# Sheet1.net
KiCad netlist of a schematic drawn in Altium Designer
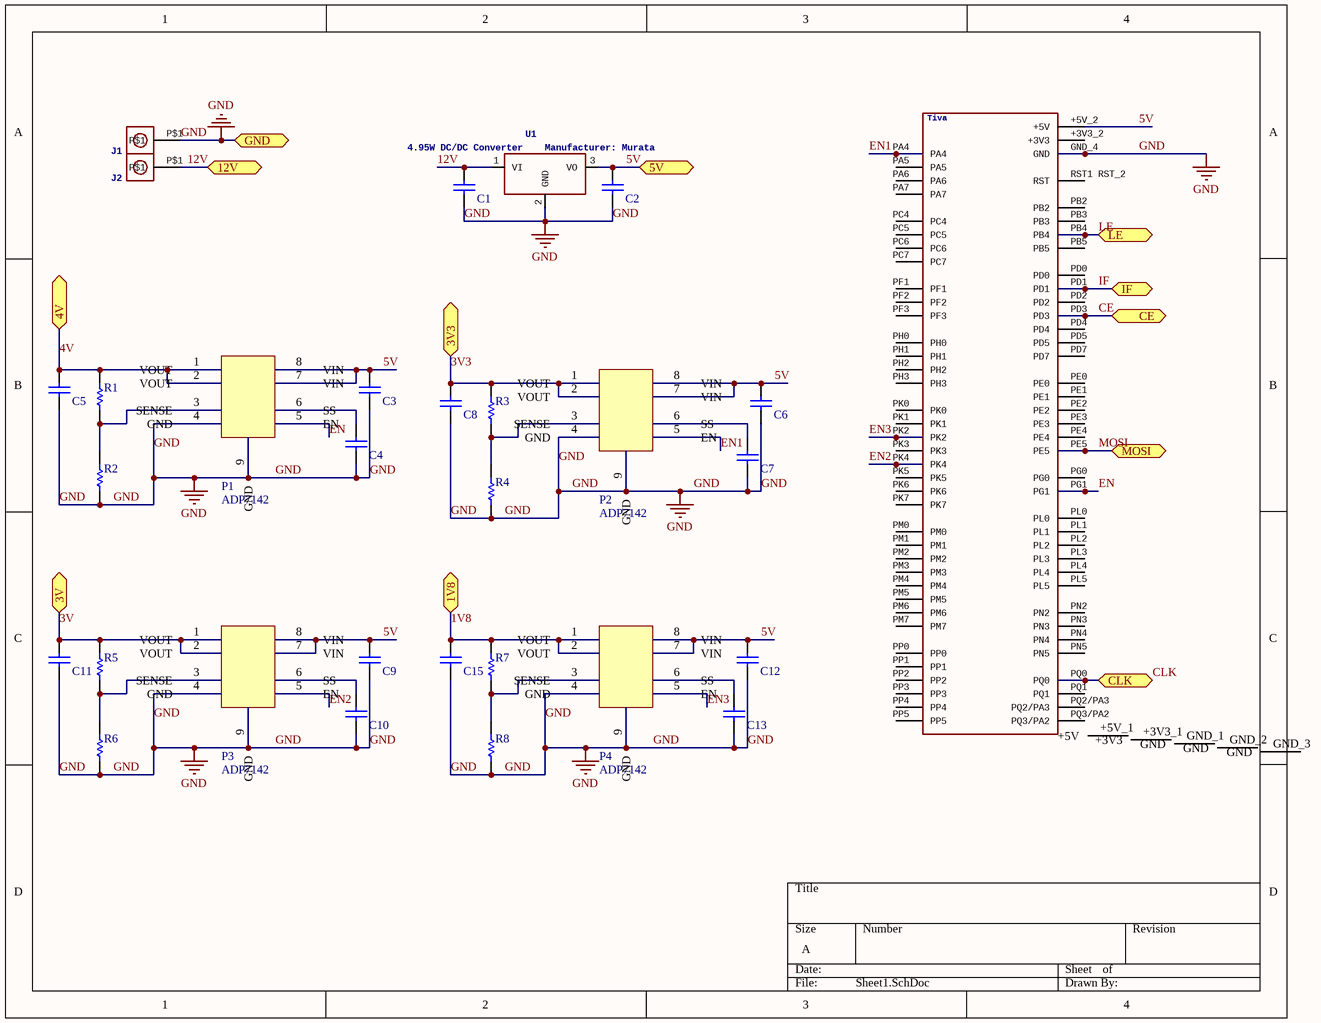
[diagram p0: Sheet1.SchDoc]

(export (version "E")
  (design (tool "Eeschema 10.0.6"))
  (components
    (comp (ref "C1")
      (value "CAP 10uF 16V 0603(1608)")
      (footprint "CAPC0603(1608)100_L")
      (description "CAP 10uF 16V ±1% 0603 (1608 Metric) Thickness 1mm SMD")
      (fields (field (name "TOLERANCE") "Â±1%"))
      (libsource (lib "Altium Content Vault") (part "CMP-1035-01744-1"))
    )
    (comp (ref "C2")
      (value "CAP 22uF 16V 0603(1608)")
      (footprint "CAPC0603(1608)100_L")
      (description "CAP 22uF 16V ±1% 0603 (1608 Metric) Thickness 1mm SMD")
      (fields (field (name "TOLERANCE") "Â±1%"))
      (libsource (lib "Altium Content Vault") (part "CMP-1035-01744-1"))
    )
    (comp (ref "C3")
      (value "CAP 2.2uF 16V 0603(1608)")
      (footprint "CAPC0603(1608)100_L")
      (description "CAP 2.2uF 16V ±1% 0603 (1608 Metric) Thickness 1mm SMD")
      (fields (field (name "TOLERANCE") "Â±1%"))
      (libsource (lib "Altium Content Vault") (part "CMP-1035-01744-1"))
    )
    (comp (ref "C4")
      (value "CAP 1nF 16V 0603(1608)")
      (footprint "CAPC0603(1608)100_L")
      (description "CAP 1nF 16V ±1% 0603 (1608 Metric) Thickness 1mm SMD")
      (fields (field (name "TOLERANCE") "Â±1%"))
      (libsource (lib "Altium Content Vault") (part "CMP-1035-01744-1"))
    )
    (comp (ref "C5")
      (value "CAP 2.2uF 16V 0603(1608)")
      (footprint "CAPC0603(1608)100_L")
      (description "CAP 2.2uF 16V ±1% 0603 (1608 Metric) Thickness 1mm SMD")
      (fields (field (name "TOLERANCE") "Â±1%"))
      (libsource (lib "Altium Content Vault") (part "CMP-1035-01744-1"))
    )
    (comp (ref "C6")
      (value "CAP 2.2uF 16V 0603(1608)")
      (footprint "CAPC0603(1608)100_L")
      (description "CAP 2.2uF 16V ±1% 0603 (1608 Metric) Thickness 1mm SMD")
      (fields (field (name "TOLERANCE") "Â±1%"))
      (libsource (lib "Altium Content Vault") (part "CMP-1035-01744-1"))
    )
    (comp (ref "C7")
      (value "CAP 1nF 16V 0603(1608)")
      (footprint "CAPC0603(1608)100_L")
      (description "CAP 1nF 16V ±1% 0603 (1608 Metric) Thickness 1mm SMD")
      (fields (field (name "TOLERANCE") "Â±1%"))
      (libsource (lib "Altium Content Vault") (part "CMP-1035-01744-1"))
    )
    (comp (ref "C8")
      (value "CAP 2.2uF 16V 0603(1608)")
      (footprint "CAPC0603(1608)100_L")
      (description "CAP 2.2uF 16V ±1% 0603 (1608 Metric) Thickness 1mm SMD")
      (fields (field (name "TOLERANCE") "Â±1%"))
      (libsource (lib "Altium Content Vault") (part "CMP-1035-01744-1"))
    )
    (comp (ref "C9")
      (value "CAP 2.2uF 16V 0603(1608)")
      (footprint "CAPC0603(1608)100_L")
      (description "CAP 2.2uF 16V ±1% 0603 (1608 Metric) Thickness 1mm SMD")
      (fields (field (name "TOLERANCE") "Â±1%"))
      (libsource (lib "Altium Content Vault") (part "CMP-1035-01744-1"))
    )
    (comp (ref "C10")
      (value "CAP 1nF 16V 0603(1608)")
      (footprint "CAPC0603(1608)100_L")
      (description "CAP 1nF 16V ±1% 0603 (1608 Metric) Thickness 1mm SMD")
      (fields (field (name "TOLERANCE") "Â±1%"))
      (libsource (lib "Altium Content Vault") (part "CMP-1035-01744-1"))
    )
    (comp (ref "C11")
      (value "CAP 2.2uF 16V 0603(1608)")
      (footprint "CAPC0603(1608)100_L")
      (description "CAP 2.2uF 16V ±1% 0603 (1608 Metric) Thickness 1mm SMD")
      (fields (field (name "TOLERANCE") "Â±1%"))
      (libsource (lib "Altium Content Vault") (part "CMP-1035-01744-1"))
    )
    (comp (ref "C12")
      (value "CAP 2.2uF 16V 0603(1608)")
      (footprint "CAPC0603(1608)100_L")
      (description "CAP 2.2uF 16V ±1% 0603 (1608 Metric) Thickness 1mm SMD")
      (fields (field (name "TOLERANCE") "Â±1%"))
      (libsource (lib "Altium Content Vault") (part "CMP-1035-01744-1"))
    )
    (comp (ref "C13")
      (value "CAP 1nF 16V 0603(1608)")
      (footprint "CAPC0603(1608)100_L")
      (description "CAP 1nF 16V ±1% 0603 (1608 Metric) Thickness 1mm SMD")
      (fields (field (name "TOLERANCE") "Â±1%"))
      (libsource (lib "Altium Content Vault") (part "CMP-1035-01744-1"))
    )
    (comp (ref "C15")
      (value "CAP 2.2uF 16V 0603(1608)")
      (footprint "CAPC0603(1608)100_L")
      (description "CAP 2.2uF 16V ±1% 0603 (1608 Metric) Thickness 1mm SMD")
      (fields (field (name "TOLERANCE") "Â±1%"))
      (libsource (lib "Altium Content Vault") (part "CMP-1035-01744-1"))
    )
    (comp (ref "J1")
      (value "http://www.powerwerx.com/anderson-powerpoles/")
      (footprint "APP45_PCB_HORIZ_RIGHT")
      (libsource (lib "MRDT-Connectors") (part "APPPP45_PCB_HORIZ_RIGHT"))
    )
    (comp (ref "J2")
      (value "http://www.powerwerx.com/anderson-powerpoles/")
      (footprint "APP45_PCB_HORIZ_RIGHT")
      (libsource (lib "MRDT-Connectors") (part "APPPP45_PCB_HORIZ_RIGHT"))
    )
    (comp (ref "P1")
      (value "ADP7142")
      (footprint "SOIC127P600X175_HS-9N")
      (libsource (lib "ADP7142") (part "ADP7142"))
    )
    (comp (ref "P2")
      (value "ADP7142")
      (footprint "SOIC127P600X175_HS-9N")
      (libsource (lib "ADP7142") (part "ADP7142"))
    )
    (comp (ref "P3")
      (value "ADP7142")
      (footprint "SOIC127P600X175_HS-9N")
      (libsource (lib "ADP7142") (part "ADP7142"))
    )
    (comp (ref "P4")
      (value "ADP7142")
      (footprint "SOIC127P600X175_HS-9N")
      (libsource (lib "ADP7142") (part "ADP7142"))
    )
    (comp (ref "R1")
      (value "500 1% 0603(1608)")
      (footprint "RESC0603(1608)_N")
      (description "500 0.1W 1% 0603 (1608 Metric)  SMD")
      (fields (field (name "POWER") "0.1 W") (field (name "TOLERANCE") "1 %"))
      (libsource (lib "Altium Content Vault") (part "CMP-1012-00736-1"))
    )
    (comp (ref "R2")
      (value "215 1% 0603(1608)")
      (footprint "RESC0603(1608)_N")
      (description "215 0.1W 1% 0603 (1608 Metric)  SMD")
      (fields (field (name "POWER") "0.1 W") (field (name "TOLERANCE") "1 %"))
      (libsource (lib "Altium Content Vault") (part "CMP-1012-00736-1"))
    )
    (comp (ref "R3")
      (value "500 1% 0603(1608)")
      (footprint "RESC0603(1608)_N")
      (description "500 0.1W 1% 0603 (1608 Metric)  SMD")
      (fields (field (name "POWER") "0.1 W") (field (name "TOLERANCE") "1 %"))
      (libsource (lib "Altium Content Vault") (part "CMP-1012-00736-1"))
    )
    (comp (ref "R4")
      (value "287 1% 0603(1608)")
      (footprint "RESC0603(1608)_N")
      (description "287 0.1W 1% 0603 (1608 Metric)  SMD")
      (fields (field (name "POWER") "0.1 W") (field (name "TOLERANCE") "1 %"))
      (libsource (lib "Altium Content Vault") (part "CMP-1012-00736-1"))
    )
    (comp (ref "R5")
      (value "500 1% 0603(1608)")
      (footprint "RESC0603(1608)_N")
      (description "500 0.1W 1% 0603 (1608 Metric)  SMD")
      (fields (field (name "POWER") "0.1 W") (field (name "TOLERANCE") "1 %"))
      (libsource (lib "Altium Content Vault") (part "CMP-1012-00736-1"))
    )
    (comp (ref "R6")
      (value "332 1% 0603(1608)")
      (footprint "RESC0603(1608)_N")
      (description "332 0.1W 1% 0603 (1608 Metric)  SMD")
      (fields (field (name "POWER") "0.1 W") (field (name "TOLERANCE") "1 %"))
      (libsource (lib "Altium Content Vault") (part "CMP-1012-00736-1"))
    )
    (comp (ref "R7")
      (value "1000 1% 0603(1608)")
      (footprint "RESC0603(1608)_N")
      (description "1000 0.1W 1% 0603 (1608 Metric)  SMD")
      (fields (field (name "POWER") "0.1 W") (field (name "TOLERANCE") "1 %"))
      (libsource (lib "Altium Content Vault") (part "CMP-1012-00736-1"))
    )
    (comp (ref "R8")
      (value "500 1% 0603(1608)")
      (footprint "RESC0603(1608)_N")
      (description "500 0.1W 1% 0603 (1608 Metric)  SMD")
      (fields (field (name "POWER") "0.1 W") (field (name "TOLERANCE") "1 %"))
      (libsource (lib "Altium Content Vault") (part "CMP-1012-00736-1"))
    )
    (comp (ref "Tiva")
      (value "TIVA C CONNECTED LAUNCHPAD")
      (footprint "TIVA-C-CONNECTED")
      (libsource (lib "MRDT-Microcontrollers") (part "TIVA-1294"))
    )
    (comp (ref "U1")
      (value "4.95W DC/DC Converter    Manufacturer: Murata")
      (footprint "OKI-78SR_HORIZ")
      (description "12 to 5V converter")
      (libsource (lib "MRDT-ICs") (part "OKI-78SR-*/1.5-W36?CH"))
    )
  )
  (nets
    (net (code "1") (name "/1V8") (class "Default")
      (node (ref "C15") (pin "1") (pinfunction "1_1") (pintype "passive"))
      (node (ref "P4") (pin "1") (pinfunction "VOUT_1") (pintype "passive"))
      (node (ref "P4") (pin "2") (pinfunction "VOUT_2") (pintype "passive"))
      (node (ref "R7") (pin "2") (pinfunction "2_2") (pintype "passive"))
    )
    (net (code "2") (name "/3V") (class "Default")
      (node (ref "C11") (pin "1") (pinfunction "1_1") (pintype "passive"))
      (node (ref "P3") (pin "1") (pinfunction "VOUT_1") (pintype "passive"))
      (node (ref "P3") (pin "2") (pinfunction "VOUT_2") (pintype "passive"))
      (node (ref "R5") (pin "2") (pinfunction "2_2") (pintype "passive"))
    )
    (net (code "3") (name "/3V3") (class "Default")
      (node (ref "C8") (pin "1") (pinfunction "1_1") (pintype "passive"))
      (node (ref "P2") (pin "1") (pinfunction "VOUT_1") (pintype "passive"))
      (node (ref "P2") (pin "2") (pinfunction "VOUT_2") (pintype "passive"))
      (node (ref "R3") (pin "2") (pinfunction "2_2") (pintype "passive"))
    )
    (net (code "4") (name "/4V") (class "Default")
      (node (ref "C5") (pin "1") (pinfunction "1_1") (pintype "passive"))
      (node (ref "P1") (pin "1") (pinfunction "VOUT_1") (pintype "passive"))
      (node (ref "P1") (pin "2") (pinfunction "VOUT_2") (pintype "passive"))
      (node (ref "R1") (pin "2") (pinfunction "2_2") (pintype "passive"))
    )
    (net (code "5") (name "/5V") (class "Default")
      (node (ref "C12") (pin "1") (pinfunction "1_1") (pintype "passive"))
      (node (ref "C2") (pin "1") (pinfunction "1_1") (pintype "passive"))
      (node (ref "C3") (pin "1") (pinfunction "1_1") (pintype "passive"))
      (node (ref "C6") (pin "1") (pinfunction "1_1") (pintype "passive"))
      (node (ref "C9") (pin "1") (pinfunction "1_1") (pintype "passive"))
      (node (ref "P1") (pin "7") (pinfunction "VIN_7") (pintype "passive"))
      (node (ref "P1") (pin "8") (pinfunction "VIN_8") (pintype "passive"))
      (node (ref "P2") (pin "7") (pinfunction "VIN_7") (pintype "passive"))
      (node (ref "P2") (pin "8") (pinfunction "VIN_8") (pintype "passive"))
      (node (ref "P3") (pin "7") (pinfunction "VIN_7") (pintype "passive"))
      (node (ref "P3") (pin "8") (pinfunction "VIN_8") (pintype "passive"))
      (node (ref "P4") (pin "7") (pinfunction "VIN_7") (pintype "passive"))
      (node (ref "P4") (pin "8") (pinfunction "VIN_8") (pintype "passive"))
      (node (ref "Tiva") (pin "+5V_2") (pinfunction "+5V_+5V_2") (pintype "passive"))
      (node (ref "U1") (pin "3") (pinfunction "VO_3") (pintype "passive"))
    )
    (net (code "6") (name "/12V") (class "Default")
      (node (ref "C1") (pin "1") (pinfunction "1_1") (pintype "passive"))
      (node (ref "J2") (pin "P$1") (pinfunction "P$1_P$1") (pintype "power_in"))
      (node (ref "U1") (pin "1") (pinfunction "VI_1") (pintype "passive"))
    )
    (net (code "7") (name "/CE") (class "Default")
      (node (ref "Tiva") (pin "PD3") (pinfunction "PD3_PD3") (pintype "passive"))
    )
    (net (code "8") (name "/CLK") (class "Default")
      (node (ref "Tiva") (pin "PQ0") (pinfunction "PQ0_PQ0") (pintype "passive"))
    )
    (net (code "9") (name "/EN") (class "Default")
      (node (ref "P1") (pin "5") (pinfunction "EN_5") (pintype "passive"))
      (node (ref "Tiva") (pin "PG1") (pinfunction "PG1_PG1") (pintype "passive"))
    )
    (net (code "10") (name "/EN1") (class "Default")
      (node (ref "P2") (pin "5") (pinfunction "EN_5") (pintype "passive"))
      (node (ref "Tiva") (pin "PA4") (pinfunction "PA4_PA4") (pintype "passive"))
    )
    (net (code "11") (name "/EN2") (class "Default")
      (node (ref "P3") (pin "5") (pinfunction "EN_5") (pintype "passive"))
      (node (ref "Tiva") (pin "PK4") (pinfunction "PK4_PK4") (pintype "passive"))
    )
    (net (code "12") (name "/EN3") (class "Default")
      (node (ref "P4") (pin "5") (pinfunction "EN_5") (pintype "passive"))
      (node (ref "Tiva") (pin "PK2") (pinfunction "PK2_PK2") (pintype "passive"))
    )
    (net (code "13") (name "/IF") (class "Default")
      (node (ref "Tiva") (pin "PD1") (pinfunction "PD1_PD1") (pintype "passive"))
    )
    (net (code "14") (name "/LE") (class "Default")
      (node (ref "Tiva") (pin "PB4") (pinfunction "PB4_PB4") (pintype "passive"))
    )
    (net (code "15") (name "/MOSI") (class "Default")
      (node (ref "Tiva") (pin "PE5") (pinfunction "PE5_PE5") (pintype "passive"))
    )
    (net (code "16") (name "GND") (class "Default")
      (node (ref "C1") (pin "2") (pinfunction "2_2") (pintype "passive"))
      (node (ref "C10") (pin "2") (pinfunction "2_2") (pintype "passive"))
      (node (ref "C11") (pin "2") (pinfunction "2_2") (pintype "passive"))
      (node (ref "C12") (pin "2") (pinfunction "2_2") (pintype "passive"))
      (node (ref "C13") (pin "2") (pinfunction "2_2") (pintype "passive"))
      (node (ref "C15") (pin "2") (pinfunction "2_2") (pintype "passive"))
      (node (ref "C2") (pin "2") (pinfunction "2_2") (pintype "passive"))
      (node (ref "C3") (pin "2") (pinfunction "2_2") (pintype "passive"))
      (node (ref "C4") (pin "2") (pinfunction "2_2") (pintype "passive"))
      (node (ref "C5") (pin "2") (pinfunction "2_2") (pintype "passive"))
      (node (ref "C6") (pin "2") (pinfunction "2_2") (pintype "passive"))
      (node (ref "C7") (pin "2") (pinfunction "2_2") (pintype "passive"))
      (node (ref "C8") (pin "2") (pinfunction "2_2") (pintype "passive"))
      (node (ref "C9") (pin "2") (pinfunction "2_2") (pintype "passive"))
      (node (ref "J1") (pin "P$1") (pinfunction "P$1_P$1") (pintype "power_in"))
      (node (ref "P1") (pin "4") (pinfunction "GND_4") (pintype "passive"))
      (node (ref "P1") (pin "9") (pinfunction "GND_9") (pintype "passive"))
      (node (ref "P2") (pin "4") (pinfunction "GND_4") (pintype "passive"))
      (node (ref "P2") (pin "9") (pinfunction "GND_9") (pintype "passive"))
      (node (ref "P3") (pin "4") (pinfunction "GND_4") (pintype "passive"))
      (node (ref "P3") (pin "9") (pinfunction "GND_9") (pintype "passive"))
      (node (ref "P4") (pin "4") (pinfunction "GND_4") (pintype "passive"))
      (node (ref "P4") (pin "9") (pinfunction "GND_9") (pintype "passive"))
      (node (ref "R2") (pin "1") (pinfunction "1_1") (pintype "passive"))
      (node (ref "R4") (pin "1") (pinfunction "1_1") (pintype "passive"))
      (node (ref "R6") (pin "1") (pinfunction "1_1") (pintype "passive"))
      (node (ref "R8") (pin "1") (pinfunction "1_1") (pintype "passive"))
      (node (ref "Tiva") (pin "GND_4") (pinfunction "GND_GND_4") (pintype "power_in"))
      (node (ref "U1") (pin "2") (pinfunction "GND_2") (pintype "power_in"))
    )
    (net (code "17") (name "Net-(P1-SENSE)") (class "Default")
      (node (ref "P1") (pin "3") (pinfunction "SENSE_3") (pintype "passive"))
      (node (ref "R1") (pin "1") (pinfunction "1_1") (pintype "passive"))
      (node (ref "R2") (pin "2") (pinfunction "2_2") (pintype "passive"))
    )
    (net (code "18") (name "Net-(P1-SS)") (class "Default")
      (node (ref "C4") (pin "1") (pinfunction "1_1") (pintype "passive"))
      (node (ref "P1") (pin "6") (pinfunction "SS_6") (pintype "passive"))
    )
    (net (code "19") (name "Net-(P2-SENSE)") (class "Default")
      (node (ref "P2") (pin "3") (pinfunction "SENSE_3") (pintype "passive"))
      (node (ref "R3") (pin "1") (pinfunction "1_1") (pintype "passive"))
      (node (ref "R4") (pin "2") (pinfunction "2_2") (pintype "passive"))
    )
    (net (code "20") (name "Net-(P2-SS)") (class "Default")
      (node (ref "C7") (pin "1") (pinfunction "1_1") (pintype "passive"))
      (node (ref "P2") (pin "6") (pinfunction "SS_6") (pintype "passive"))
    )
    (net (code "21") (name "Net-(P3-SENSE)") (class "Default")
      (node (ref "P3") (pin "3") (pinfunction "SENSE_3") (pintype "passive"))
      (node (ref "R5") (pin "1") (pinfunction "1_1") (pintype "passive"))
      (node (ref "R6") (pin "2") (pinfunction "2_2") (pintype "passive"))
    )
    (net (code "22") (name "Net-(P3-SS)") (class "Default")
      (node (ref "C10") (pin "1") (pinfunction "1_1") (pintype "passive"))
      (node (ref "P3") (pin "6") (pinfunction "SS_6") (pintype "passive"))
    )
    (net (code "23") (name "Net-(P4-SENSE)") (class "Default")
      (node (ref "P4") (pin "3") (pinfunction "SENSE_3") (pintype "passive"))
      (node (ref "R7") (pin "1") (pinfunction "1_1") (pintype "passive"))
      (node (ref "R8") (pin "2") (pinfunction "2_2") (pintype "passive"))
    )
    (net (code "24") (name "Net-(P4-SS)") (class "Default")
      (node (ref "C13") (pin "1") (pinfunction "1_1") (pintype "passive"))
      (node (ref "P4") (pin "6") (pinfunction "SS_6") (pintype "passive"))
    )
    (net (code "25") (name "unconnected-(Tiva-+3V3-Pad+3V3_1)") (class "Default")
      (node (ref "Tiva") (pin "+3V3_1") (pinfunction "+3V3_+3V3_1") (pintype "passive"))
    )
    (net (code "26") (name "unconnected-(Tiva-+3V3-Pad+3V3_2)") (class "Default")
      (node (ref "Tiva") (pin "+3V3_2") (pinfunction "+3V3_+3V3_2") (pintype "passive"))
    )
    (net (code "27") (name "unconnected-(Tiva-+5V-Pad+5V_1)") (class "Default")
      (node (ref "Tiva") (pin "+5V_1") (pinfunction "+5V_+5V_1") (pintype "passive"))
    )
    (net (code "28") (name "unconnected-(Tiva-GND-PadGND_1)") (class "Default")
      (node (ref "Tiva") (pin "GND_1") (pinfunction "GND_GND_1") (pintype "passive"))
    )
    (net (code "29") (name "unconnected-(Tiva-GND-PadGND_2)") (class "Default")
      (node (ref "Tiva") (pin "GND_2") (pinfunction "GND_GND_2") (pintype "passive"))
    )
    (net (code "30") (name "unconnected-(Tiva-GND-PadGND_3)") (class "Default")
      (node (ref "Tiva") (pin "GND_3") (pinfunction "GND_GND_3") (pintype "passive"))
    )
    (net (code "31") (name "unconnected-(Tiva-PadPA5)") (class "Default")
      (node (ref "Tiva") (pin "PA5") (pinfunction "PA5_PA5") (pintype "passive"))
    )
    (net (code "32") (name "unconnected-(Tiva-PadPA6)") (class "Default")
      (node (ref "Tiva") (pin "PA6") (pinfunction "PA6_PA6") (pintype "passive"))
    )
    (net (code "33") (name "unconnected-(Tiva-PadPA7)") (class "Default")
      (node (ref "Tiva") (pin "PA7") (pinfunction "PA7_PA7") (pintype "passive"))
    )
    (net (code "34") (name "unconnected-(Tiva-PadPB2)") (class "Default")
      (node (ref "Tiva") (pin "PB2") (pinfunction "PB2_PB2") (pintype "passive"))
    )
    (net (code "35") (name "unconnected-(Tiva-PadPB3)") (class "Default")
      (node (ref "Tiva") (pin "PB3") (pinfunction "PB3_PB3") (pintype "passive"))
    )
    (net (code "36") (name "unconnected-(Tiva-PadPB5)") (class "Default")
      (node (ref "Tiva") (pin "PB5") (pinfunction "PB5_PB5") (pintype "passive"))
    )
    (net (code "37") (name "unconnected-(Tiva-PadPC4)") (class "Default")
      (node (ref "Tiva") (pin "PC4") (pinfunction "PC4_PC4") (pintype "passive"))
    )
    (net (code "38") (name "unconnected-(Tiva-PadPC5)") (class "Default")
      (node (ref "Tiva") (pin "PC5") (pinfunction "PC5_PC5") (pintype "passive"))
    )
    (net (code "39") (name "unconnected-(Tiva-PadPC6)") (class "Default")
      (node (ref "Tiva") (pin "PC6") (pinfunction "PC6_PC6") (pintype "passive"))
    )
    (net (code "40") (name "unconnected-(Tiva-PadPC7)") (class "Default")
      (node (ref "Tiva") (pin "PC7") (pinfunction "PC7_PC7") (pintype "passive"))
    )
    (net (code "41") (name "unconnected-(Tiva-PadPD0)") (class "Default")
      (node (ref "Tiva") (pin "PD0") (pinfunction "PD0_PD0") (pintype "passive"))
    )
    (net (code "42") (name "unconnected-(Tiva-PadPD2)") (class "Default")
      (node (ref "Tiva") (pin "PD2") (pinfunction "PD2_PD2") (pintype "passive"))
    )
    (net (code "43") (name "unconnected-(Tiva-PadPD4)") (class "Default")
      (node (ref "Tiva") (pin "PD4") (pinfunction "PD4_PD4") (pintype "passive"))
    )
    (net (code "44") (name "unconnected-(Tiva-PadPD5)") (class "Default")
      (node (ref "Tiva") (pin "PD5") (pinfunction "PD5_PD5") (pintype "passive"))
    )
    (net (code "45") (name "unconnected-(Tiva-PadPD7)") (class "Default")
      (node (ref "Tiva") (pin "PD7") (pinfunction "PD7_PD7") (pintype "passive"))
    )
    (net (code "46") (name "unconnected-(Tiva-PadPE0)") (class "Default")
      (node (ref "Tiva") (pin "PE0") (pinfunction "PE0_PE0") (pintype "passive"))
    )
    (net (code "47") (name "unconnected-(Tiva-PadPE1)") (class "Default")
      (node (ref "Tiva") (pin "PE1") (pinfunction "PE1_PE1") (pintype "passive"))
    )
    (net (code "48") (name "unconnected-(Tiva-PadPE2)") (class "Default")
      (node (ref "Tiva") (pin "PE2") (pinfunction "PE2_PE2") (pintype "passive"))
    )
    (net (code "49") (name "unconnected-(Tiva-PadPE3)") (class "Default")
      (node (ref "Tiva") (pin "PE3") (pinfunction "PE3_PE3") (pintype "passive"))
    )
    (net (code "50") (name "unconnected-(Tiva-PadPE4)") (class "Default")
      (node (ref "Tiva") (pin "PE4") (pinfunction "PE4_PE4") (pintype "passive"))
    )
    (net (code "51") (name "unconnected-(Tiva-PadPF1)") (class "Default")
      (node (ref "Tiva") (pin "PF1") (pinfunction "PF1_PF1") (pintype "passive"))
    )
    (net (code "52") (name "unconnected-(Tiva-PadPF2)") (class "Default")
      (node (ref "Tiva") (pin "PF2") (pinfunction "PF2_PF2") (pintype "passive"))
    )
    (net (code "53") (name "unconnected-(Tiva-PadPF3)") (class "Default")
      (node (ref "Tiva") (pin "PF3") (pinfunction "PF3_PF3") (pintype "passive"))
    )
    (net (code "54") (name "unconnected-(Tiva-PadPG0)") (class "Default")
      (node (ref "Tiva") (pin "PG0") (pinfunction "PG0_PG0") (pintype "passive"))
    )
    (net (code "55") (name "unconnected-(Tiva-PadPH0)") (class "Default")
      (node (ref "Tiva") (pin "PH0") (pinfunction "PH0_PH0") (pintype "passive"))
    )
    (net (code "56") (name "unconnected-(Tiva-PadPH1)") (class "Default")
      (node (ref "Tiva") (pin "PH1") (pinfunction "PH1_PH1") (pintype "passive"))
    )
    (net (code "57") (name "unconnected-(Tiva-PadPH2)") (class "Default")
      (node (ref "Tiva") (pin "PH2") (pinfunction "PH2_PH2") (pintype "passive"))
    )
    (net (code "58") (name "unconnected-(Tiva-PadPH3)") (class "Default")
      (node (ref "Tiva") (pin "PH3") (pinfunction "PH3_PH3") (pintype "passive"))
    )
    (net (code "59") (name "unconnected-(Tiva-PadPK0)") (class "Default")
      (node (ref "Tiva") (pin "PK0") (pinfunction "PK0_PK0") (pintype "passive"))
    )
    (net (code "60") (name "unconnected-(Tiva-PadPK1)") (class "Default")
      (node (ref "Tiva") (pin "PK1") (pinfunction "PK1_PK1") (pintype "passive"))
    )
    (net (code "61") (name "unconnected-(Tiva-PadPK3)") (class "Default")
      (node (ref "Tiva") (pin "PK3") (pinfunction "PK3_PK3") (pintype "passive"))
    )
    (net (code "62") (name "unconnected-(Tiva-PadPK5)") (class "Default")
      (node (ref "Tiva") (pin "PK5") (pinfunction "PK5_PK5") (pintype "passive"))
    )
    (net (code "63") (name "unconnected-(Tiva-PadPK6)") (class "Default")
      (node (ref "Tiva") (pin "PK6") (pinfunction "PK6_PK6") (pintype "passive"))
    )
    (net (code "64") (name "unconnected-(Tiva-PadPK7)") (class "Default")
      (node (ref "Tiva") (pin "PK7") (pinfunction "PK7_PK7") (pintype "passive"))
    )
    (net (code "65") (name "unconnected-(Tiva-PadPL0)") (class "Default")
      (node (ref "Tiva") (pin "PL0") (pinfunction "PL0_PL0") (pintype "passive"))
    )
    (net (code "66") (name "unconnected-(Tiva-PadPL1)") (class "Default")
      (node (ref "Tiva") (pin "PL1") (pinfunction "PL1_PL1") (pintype "passive"))
    )
    (net (code "67") (name "unconnected-(Tiva-PadPL2)") (class "Default")
      (node (ref "Tiva") (pin "PL2") (pinfunction "PL2_PL2") (pintype "passive"))
    )
    (net (code "68") (name "unconnected-(Tiva-PadPL3)") (class "Default")
      (node (ref "Tiva") (pin "PL3") (pinfunction "PL3_PL3") (pintype "passive"))
    )
    (net (code "69") (name "unconnected-(Tiva-PadPL4)") (class "Default")
      (node (ref "Tiva") (pin "PL4") (pinfunction "PL4_PL4") (pintype "passive"))
    )
    (net (code "70") (name "unconnected-(Tiva-PadPL5)") (class "Default")
      (node (ref "Tiva") (pin "PL5") (pinfunction "PL5_PL5") (pintype "passive"))
    )
    (net (code "71") (name "unconnected-(Tiva-PadPM0)") (class "Default")
      (node (ref "Tiva") (pin "PM0") (pinfunction "PM0_PM0") (pintype "passive"))
    )
    (net (code "72") (name "unconnected-(Tiva-PadPM1)") (class "Default")
      (node (ref "Tiva") (pin "PM1") (pinfunction "PM1_PM1") (pintype "passive"))
    )
    (net (code "73") (name "unconnected-(Tiva-PadPM2)") (class "Default")
      (node (ref "Tiva") (pin "PM2") (pinfunction "PM2_PM2") (pintype "passive"))
    )
    (net (code "74") (name "unconnected-(Tiva-PadPM3)") (class "Default")
      (node (ref "Tiva") (pin "PM3") (pinfunction "PM3_PM3") (pintype "passive"))
    )
    (net (code "75") (name "unconnected-(Tiva-PadPM4)") (class "Default")
      (node (ref "Tiva") (pin "PM4") (pinfunction "PM4_PM4") (pintype "passive"))
    )
    (net (code "76") (name "unconnected-(Tiva-PadPM5)") (class "Default")
      (node (ref "Tiva") (pin "PM5") (pinfunction "PM5_PM5") (pintype "passive"))
    )
    (net (code "77") (name "unconnected-(Tiva-PadPM6)") (class "Default")
      (node (ref "Tiva") (pin "PM6") (pinfunction "PM6_PM6") (pintype "passive"))
    )
    (net (code "78") (name "unconnected-(Tiva-PadPM7)") (class "Default")
      (node (ref "Tiva") (pin "PM7") (pinfunction "PM7_PM7") (pintype "passive"))
    )
    (net (code "79") (name "unconnected-(Tiva-PadPN2)") (class "Default")
      (node (ref "Tiva") (pin "PN2") (pinfunction "PN2_PN2") (pintype "passive"))
    )
    (net (code "80") (name "unconnected-(Tiva-PadPN3)") (class "Default")
      (node (ref "Tiva") (pin "PN3") (pinfunction "PN3_PN3") (pintype "passive"))
    )
    (net (code "81") (name "unconnected-(Tiva-PadPN4)") (class "Default")
      (node (ref "Tiva") (pin "PN4") (pinfunction "PN4_PN4") (pintype "passive"))
    )
    (net (code "82") (name "unconnected-(Tiva-PadPN5)") (class "Default")
      (node (ref "Tiva") (pin "PN5") (pinfunction "PN5_PN5") (pintype "passive"))
    )
    (net (code "83") (name "unconnected-(Tiva-PadPP0)") (class "Default")
      (node (ref "Tiva") (pin "PP0") (pinfunction "PP0_PP0") (pintype "passive"))
    )
    (net (code "84") (name "unconnected-(Tiva-PadPP1)") (class "Default")
      (node (ref "Tiva") (pin "PP1") (pinfunction "PP1_PP1") (pintype "passive"))
    )
    (net (code "85") (name "unconnected-(Tiva-PadPP2)") (class "Default")
      (node (ref "Tiva") (pin "PP2") (pinfunction "PP2_PP2") (pintype "passive"))
    )
    (net (code "86") (name "unconnected-(Tiva-PadPP3)") (class "Default")
      (node (ref "Tiva") (pin "PP3") (pinfunction "PP3_PP3") (pintype "passive"))
    )
    (net (code "87") (name "unconnected-(Tiva-PadPP4)") (class "Default")
      (node (ref "Tiva") (pin "PP4") (pinfunction "PP4_PP4") (pintype "passive"))
    )
    (net (code "88") (name "unconnected-(Tiva-PadPP5)") (class "Default")
      (node (ref "Tiva") (pin "PP5") (pinfunction "PP5_PP5") (pintype "passive"))
    )
    (net (code "89") (name "unconnected-(Tiva-PadPQ1)") (class "Default")
      (node (ref "Tiva") (pin "PQ1") (pinfunction "PQ1_PQ1") (pintype "passive"))
    )
    (net (code "90") (name "unconnected-(Tiva-PadPQ2{slash}PA3)") (class "Default")
      (node (ref "Tiva") (pin "PQ2/PA3") (pinfunction "PQ2/PA3_PQ2/PA3") (pintype "passive"))
    )
    (net (code "91") (name "unconnected-(Tiva-PadPQ3{slash}PA2)") (class "Default")
      (node (ref "Tiva") (pin "PQ3/PA2") (pinfunction "PQ3/PA2_PQ3/PA2") (pintype "passive"))
    )
    (net (code "92") (name "unconnected-(Tiva-RST-PadRST1_RST_2)") (class "Default")
      (node (ref "Tiva") (pin "RST1_RST_2") (pinfunction "RST_RST1_RST_2") (pintype "passive"))
    )
  )
)
